# Ethernet.net
KiCad netlist of a schematic drawn in Altium Designer
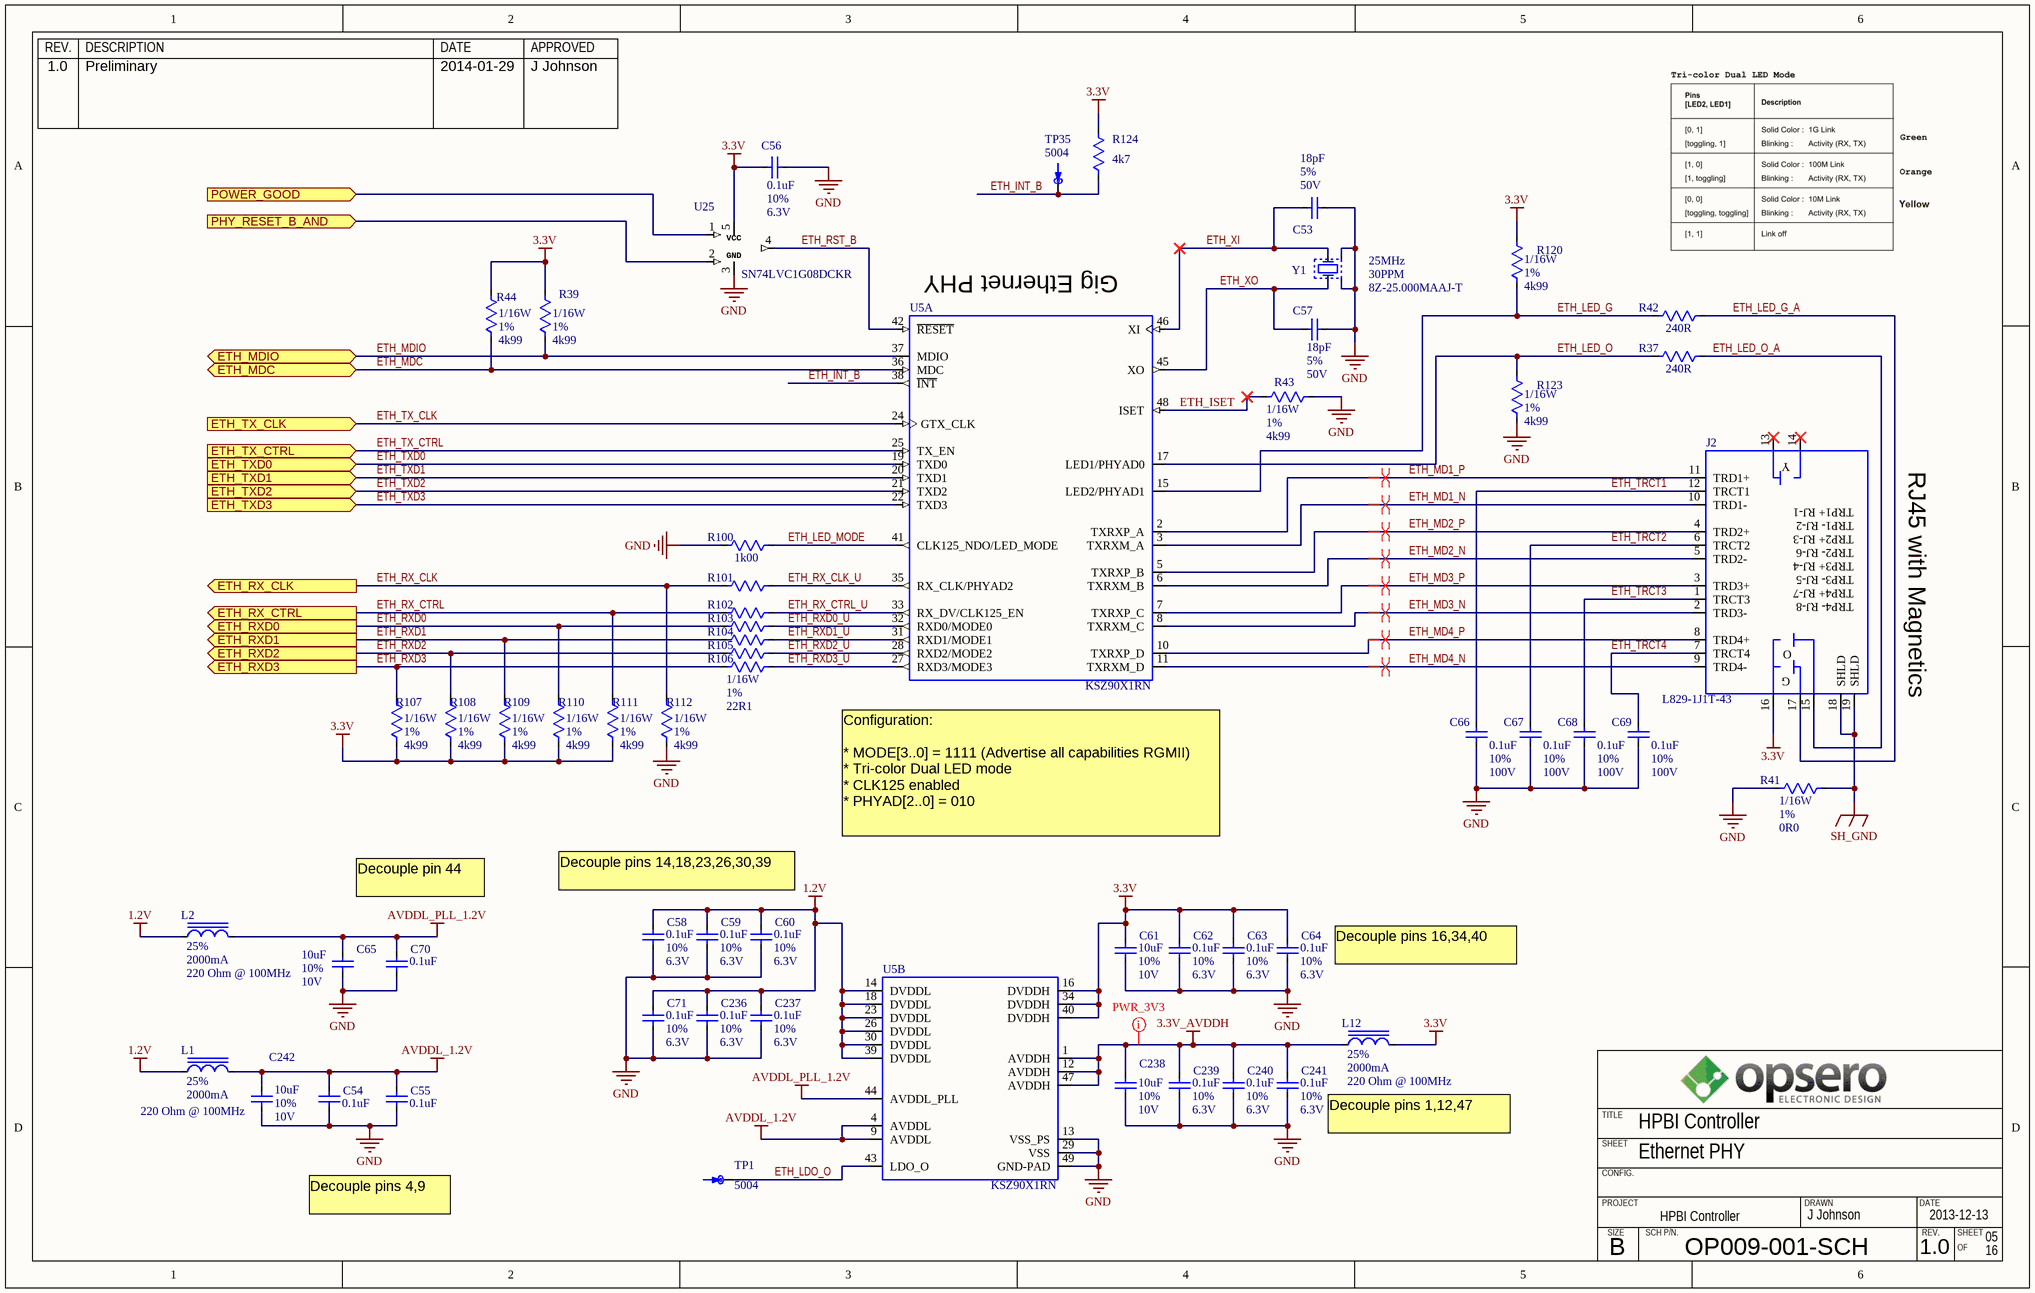
[diagram p0: Ethernet.SchDoc]

(export (version "E")
  (design (tool "Eeschema 10.0.6"))
  (components
    (comp (ref "C53")
      (value "18pF")
      (footprint "CAPC1005X33N")
      (description "Capacitor ceramic, C0G (NP0), 18pF, 50V, 5%, -55 to +125 C, EIA0402")
      (fields
        (field (name "TOLERANCE") "5%")
        (field (name "VOLTAGE") "50V")
        (field (name "Comment") "CAPACITOR_NP_TYPE1")
      )
      (libsource (lib "parts") (part "CAPACITOR_NP_TYPE1"))
    )
    (comp (ref "C54")
      (value "0.1uF")
      (footprint "CAPC0603X33N")
      (description "Capacitor ceramic, X5R, 0.1uF, 6.3V, 10%, -55 to +125 C, EIA0201")
      (fields (field (name "TOLERANCE") "10%") (field (name "VOLTAGE") "6.3V"))
      (libsource (lib "parts") (part "CAPACITOR_NP_TYPE1"))
    )
    (comp (ref "C55")
      (value "0.1uF")
      (footprint "CAPC0603X33N")
      (description "Capacitor ceramic, X5R, 0.1uF, 6.3V, 10%, -55 to +125 C, EIA0201")
      (fields (field (name "TOLERANCE") "10%") (field (name "VOLTAGE") "6.3V"))
      (libsource (lib "parts") (part "CAPACITOR_NP_TYPE1"))
    )
    (comp (ref "C56")
      (value "0.1uF")
      (footprint "CAPC0603X33N")
      (description "Capacitor ceramic, X5R, 0.1uF, 6.3V, 10%, -55 to +125 C, EIA0201")
      (fields
        (field (name "TOLERANCE") "10%")
        (field (name "VOLTAGE") "6.3V")
        (field (name "Comment") "CAPACITOR_NP_TYPE1")
      )
      (libsource (lib "parts") (part "CAPACITOR_NP_TYPE1"))
    )
    (comp (ref "C57")
      (value "18pF")
      (footprint "CAPC1005X33N")
      (description "Capacitor ceramic, C0G (NP0), 18pF, 50V, 5%, -55 to +125 C, EIA0402")
      (fields
        (field (name "TOLERANCE") "5%")
        (field (name "VOLTAGE") "50V")
        (field (name "Comment") "CAPACITOR_NP_TYPE1")
      )
      (libsource (lib "parts") (part "CAPACITOR_NP_TYPE1"))
    )
    (comp (ref "C58")
      (value "0.1uF")
      (footprint "CAPC0603X33N")
      (description "Capacitor ceramic, X5R, 0.1uF, 6.3V, 10%, -55 to +125 C, EIA0201")
      (fields
        (field (name "TOLERANCE") "10%")
        (field (name "VOLTAGE") "6.3V")
        (field (name "Comment") "CAPACITOR_NP_TYPE1")
      )
      (libsource (lib "parts") (part "CAPACITOR_NP_TYPE1"))
    )
    (comp (ref "C59")
      (value "0.1uF")
      (footprint "CAPC0603X33N")
      (description "Capacitor ceramic, X5R, 0.1uF, 6.3V, 10%, -55 to +125 C, EIA0201")
      (fields
        (field (name "TOLERANCE") "10%")
        (field (name "VOLTAGE") "6.3V")
        (field (name "Comment") "CAPACITOR_NP_TYPE1")
      )
      (libsource (lib "parts") (part "CAPACITOR_NP_TYPE1"))
    )
    (comp (ref "C60")
      (value "0.1uF")
      (footprint "CAPC0603X33N")
      (description "Capacitor ceramic, X5R, 0.1uF, 6.3V, 10%, -55 to +125 C, EIA0201")
      (fields
        (field (name "TOLERANCE") "10%")
        (field (name "VOLTAGE") "6.3V")
        (field (name "Comment") "CAPACITOR_NP_TYPE1")
      )
      (libsource (lib "parts") (part "CAPACITOR_NP_TYPE1"))
    )
    (comp (ref "C61")
      (value "10uF")
      (footprint "CAPC1608X38N")
      (description "Capacitor ceramic, X5R, 10uF, 10V, 10%, -55 to +85 C, EIA0603")
      (fields
        (field (name "TOLERANCE") "10%")
        (field (name "VOLTAGE") "10V")
        (field (name "Comment") "CAPACITOR_NP_TYPE1")
      )
      (libsource (lib "parts") (part "CAPACITOR_NP_TYPE1"))
    )
    (comp (ref "C62")
      (value "0.1uF")
      (footprint "CAPC0603X33N")
      (description "Capacitor ceramic, X5R, 0.1uF, 6.3V, 10%, -55 to +125 C, EIA0201")
      (fields
        (field (name "TOLERANCE") "10%")
        (field (name "VOLTAGE") "6.3V")
        (field (name "Comment") "CAPACITOR_NP_TYPE1")
      )
      (libsource (lib "parts") (part "CAPACITOR_NP_TYPE1"))
    )
    (comp (ref "C63")
      (value "0.1uF")
      (footprint "CAPC0603X33N")
      (description "Capacitor ceramic, X5R, 0.1uF, 6.3V, 10%, -55 to +125 C, EIA0201")
      (fields
        (field (name "TOLERANCE") "10%")
        (field (name "VOLTAGE") "6.3V")
        (field (name "Comment") "CAPACITOR_NP_TYPE1")
      )
      (libsource (lib "parts") (part "CAPACITOR_NP_TYPE1"))
    )
    (comp (ref "C64")
      (value "0.1uF")
      (footprint "CAPC0603X33N")
      (description "Capacitor ceramic, X5R, 0.1uF, 6.3V, 10%, -55 to +125 C, EIA0201")
      (fields
        (field (name "TOLERANCE") "10%")
        (field (name "VOLTAGE") "6.3V")
        (field (name "Comment") "CAPACITOR_NP_TYPE1")
      )
      (libsource (lib "parts") (part "CAPACITOR_NP_TYPE1"))
    )
    (comp (ref "C65")
      (value "10uF")
      (footprint "CAPC1608X38N")
      (description "Capacitor ceramic, X5R, 10uF, 10V, 10%, -55 to +85 C, EIA0603")
      (fields
        (field (name "TOLERANCE") "10%")
        (field (name "VOLTAGE") "10V")
        (field (name "Comment") "CAPACITOR_NP_TYPE1")
      )
      (libsource (lib "parts") (part "CAPACITOR_NP_TYPE1"))
    )
    (comp (ref "C66")
      (value "0.1uF")
      (footprint "CAPC1608X38N")
      (description "Capacitor ceramic, X7R, 0.1uF, 100V, 10%, -55 to +125 C, EIA0603")
      (fields
        (field (name "TOLERANCE") "10%")
        (field (name "VOLTAGE") "100V")
        (field (name "Comment") "CAPACITOR_NP_TYPE1")
      )
      (libsource (lib "parts") (part "CAPACITOR_NP_TYPE1"))
    )
    (comp (ref "C67")
      (value "0.1uF")
      (footprint "CAPC1608X38N")
      (description "Capacitor ceramic, X7R, 0.1uF, 100V, 10%, -55 to +125 C, EIA0603")
      (fields
        (field (name "TOLERANCE") "10%")
        (field (name "VOLTAGE") "100V")
        (field (name "Comment") "CAPACITOR_NP_TYPE1")
      )
      (libsource (lib "parts") (part "CAPACITOR_NP_TYPE1"))
    )
    (comp (ref "C68")
      (value "0.1uF")
      (footprint "CAPC1608X38N")
      (description "Capacitor ceramic, X7R, 0.1uF, 100V, 10%, -55 to +125 C, EIA0603")
      (fields
        (field (name "TOLERANCE") "10%")
        (field (name "VOLTAGE") "100V")
        (field (name "Comment") "CAPACITOR_NP_TYPE1")
      )
      (libsource (lib "parts") (part "CAPACITOR_NP_TYPE1"))
    )
    (comp (ref "C69")
      (value "0.1uF")
      (footprint "CAPC1608X38N")
      (description "Capacitor ceramic, X7R, 0.1uF, 100V, 10%, -55 to +125 C, EIA0603")
      (fields
        (field (name "TOLERANCE") "10%")
        (field (name "VOLTAGE") "100V")
        (field (name "Comment") "CAPACITOR_NP_TYPE1")
      )
      (libsource (lib "parts") (part "CAPACITOR_NP_TYPE1"))
    )
    (comp (ref "C70")
      (value "0.1uF")
      (footprint "CAPC0603X33N")
      (description "Capacitor ceramic, X5R, 0.1uF, 6.3V, 10%, -55 to +125 C, EIA0201")
      (fields (field (name "TOLERANCE") "10%") (field (name "VOLTAGE") "6.3V"))
      (libsource (lib "parts") (part "CAPACITOR_NP_TYPE1"))
    )
    (comp (ref "C71")
      (value "0.1uF")
      (footprint "CAPC0603X33N")
      (description "Capacitor ceramic, X5R, 0.1uF, 6.3V, 10%, -55 to +125 C, EIA0201")
      (fields
        (field (name "TOLERANCE") "10%")
        (field (name "VOLTAGE") "6.3V")
        (field (name "Comment") "CAPACITOR_NP_TYPE1")
      )
      (libsource (lib "parts") (part "CAPACITOR_NP_TYPE1"))
    )
    (comp (ref "C236")
      (value "0.1uF")
      (footprint "CAPC0603X33N")
      (description "Capacitor ceramic, X5R, 0.1uF, 6.3V, 10%, -55 to +125 C, EIA0201")
      (fields
        (field (name "TOLERANCE") "10%")
        (field (name "VOLTAGE") "6.3V")
        (field (name "Comment") "CAPACITOR_NP_TYPE1")
      )
      (libsource (lib "parts") (part "CAPACITOR_NP_TYPE1"))
    )
    (comp (ref "C237")
      (value "0.1uF")
      (footprint "CAPC0603X33N")
      (description "Capacitor ceramic, X5R, 0.1uF, 6.3V, 10%, -55 to +125 C, EIA0201")
      (fields
        (field (name "TOLERANCE") "10%")
        (field (name "VOLTAGE") "6.3V")
        (field (name "Comment") "CAPACITOR_NP_TYPE1")
      )
      (libsource (lib "parts") (part "CAPACITOR_NP_TYPE1"))
    )
    (comp (ref "C238")
      (value "10uF")
      (footprint "CAPC1608X38N")
      (description "Capacitor ceramic, X5R, 10uF, 10V, 10%, -55 to +85 C, EIA0603")
      (fields
        (field (name "TOLERANCE") "10%")
        (field (name "VOLTAGE") "10V")
        (field (name "Comment") "CAPACITOR_NP_TYPE1")
      )
      (libsource (lib "parts") (part "CAPACITOR_NP_TYPE1"))
    )
    (comp (ref "C239")
      (value "0.1uF")
      (footprint "CAPC0603X33N")
      (description "Capacitor ceramic, X5R, 0.1uF, 6.3V, 10%, -55 to +125 C, EIA0201")
      (fields
        (field (name "TOLERANCE") "10%")
        (field (name "VOLTAGE") "6.3V")
        (field (name "Comment") "CAPACITOR_NP_TYPE1")
      )
      (libsource (lib "parts") (part "CAPACITOR_NP_TYPE1"))
    )
    (comp (ref "C240")
      (value "0.1uF")
      (footprint "CAPC0603X33N")
      (description "Capacitor ceramic, X5R, 0.1uF, 6.3V, 10%, -55 to +125 C, EIA0201")
      (fields
        (field (name "TOLERANCE") "10%")
        (field (name "VOLTAGE") "6.3V")
        (field (name "Comment") "CAPACITOR_NP_TYPE1")
      )
      (libsource (lib "parts") (part "CAPACITOR_NP_TYPE1"))
    )
    (comp (ref "C241")
      (value "0.1uF")
      (footprint "CAPC0603X33N")
      (description "Capacitor ceramic, X5R, 0.1uF, 6.3V, 10%, -55 to +125 C, EIA0201")
      (fields
        (field (name "TOLERANCE") "10%")
        (field (name "VOLTAGE") "6.3V")
        (field (name "Comment") "CAPACITOR_NP_TYPE1")
      )
      (libsource (lib "parts") (part "CAPACITOR_NP_TYPE1"))
    )
    (comp (ref "C242")
      (value "10uF")
      (footprint "CAPC1608X38N")
      (description "Capacitor ceramic, X5R, 10uF, 10V, 10%, -55 to +85 C, EIA0603")
      (fields
        (field (name "TOLERANCE") "10%")
        (field (name "VOLTAGE") "10V")
        (field (name "Comment") "CAPACITOR_NP_TYPE1")
      )
      (libsource (lib "parts") (part "CAPACITOR_NP_TYPE1"))
    )
    (comp (ref "J2")
      (value "L829-1J1T-43")
      (footprint "L829-1J1T-43")
      (description "Connector RJ45,10/100/1000, with Mag & 3 LED G/O/Y")
      (fields (field (name "POWER") "Pow") (field (name "VOLTAGE") "Vol"))
      (libsource (lib "parts") (part "CON_J_RJ45_MAG_TYPE_2"))
    )
    (comp (ref "L1")
      (value "220 Ohm @ 100MHz")
      (footprint "INDC2012X85N")
      (description "Ferrite chip, 220 Ohm @ 100MHz, 2000mA, 25%, -55 to +125 C, 0805")
      (fields
        (field (name "TOLERANCE") "25%")
        (field (name "CURRENT") "2000mA")
        (field (name "Comment") "INDUCTOR_CORE_TYPE1")
      )
      (libsource (lib "parts") (part "INDUCTOR_CORE_TYPE1"))
    )
    (comp (ref "L2")
      (value "220 Ohm @ 100MHz")
      (footprint "INDC2012X85N")
      (description "Ferrite chip, 220 Ohm @ 100MHz, 2000mA, 25%, -55 to +125 C, 0805")
      (fields
        (field (name "TOLERANCE") "25%")
        (field (name "CURRENT") "2000mA")
        (field (name "Comment") "INDUCTOR_CORE_TYPE1")
      )
      (libsource (lib "parts") (part "INDUCTOR_CORE_TYPE1"))
    )
    (comp (ref "L12")
      (value "220 Ohm @ 100MHz")
      (footprint "INDC2012X85N")
      (description "Ferrite chip, 220 Ohm @ 100MHz, 2000mA, 25%, -55 to +125 C, 0805")
      (fields
        (field (name "TOLERANCE") "25%")
        (field (name "CURRENT") "2000mA")
        (field (name "Comment") "INDUCTOR_CORE_TYPE1")
      )
      (libsource (lib "parts") (part "INDUCTOR_CORE_TYPE1"))
    )
    (comp (ref "R37")
      (value "240R")
      (footprint "RESC1005X33N")
      (description "Resistor, 240R, 1/16W, 1%, -50 to +155 C, EIA0402, EIA(M)1005")
      (fields (field (name "VOLTAGE") "50V") (field (name "POWER") "1/16W"))
      (libsource (lib "parts") (part "RESISTOR_TYPE1"))
    )
    (comp (ref "R39")
      (value "4k99")
      (footprint "RESC1005X33N")
      (description "Resistor, 4k99, 1/16W, 1%, -50 to +155 C, EIA0402, EIA(M)1005")
      (fields (field (name "VOLTAGE") "50V") (field (name "POWER") "1/16W") (field (name "TOLERANCE") "1%"))
      (libsource (lib "parts") (part "RESISTOR_TYPE1"))
    )
    (comp (ref "R41")
      (value "0R0")
      (footprint "RESC1005X33N")
      (description "Resistor, 0R0, 1/16W, 1%, -50 to +155 C, EIA0402, EIA(M)1005")
      (fields (field (name "VOLTAGE") "50V") (field (name "POWER") "1/16W") (field (name "TOLERANCE") "1%"))
      (libsource (lib "parts") (part "RESISTOR_TYPE1"))
    )
    (comp (ref "R42")
      (value "240R")
      (footprint "RESC1005X33N")
      (description "Resistor, 240R, 1/16W, 1%, -50 to +155 C, EIA0402, EIA(M)1005")
      (fields (field (name "VOLTAGE") "50V") (field (name "POWER") "1/16W"))
      (libsource (lib "parts") (part "RESISTOR_TYPE1"))
    )
    (comp (ref "R43")
      (value "4k99")
      (footprint "RESC1005X33N")
      (description "Resistor, 4k99, 1/16W, 1%, -50 to +155 C, EIA0402, EIA(M)1005")
      (fields (field (name "VOLTAGE") "50V") (field (name "POWER") "1/16W") (field (name "TOLERANCE") "1%"))
      (libsource (lib "parts") (part "RESISTOR_TYPE1"))
    )
    (comp (ref "R44")
      (value "4k99")
      (footprint "RESC1005X33N")
      (description "Resistor, 4k99, 1/16W, 1%, -50 to +155 C, EIA0402, EIA(M)1005")
      (fields (field (name "VOLTAGE") "50V") (field (name "POWER") "1/16W") (field (name "TOLERANCE") "1%"))
      (libsource (lib "parts") (part "RESISTOR_TYPE1"))
    )
    (comp (ref "R100")
      (value "1k00")
      (footprint "RESC1005X33N")
      (description "Resistor, 1k00, 1/16W, 1%, -55 to +155 C, EIA0402")
      (fields (field (name "VOLTAGE") "50V") (field (name "POWER") "1/16W"))
      (libsource (lib "parts") (part "RESISTOR_TYPE1"))
    )
    (comp (ref "R101")
      (value "*")
      (footprint "RESC1005X33N")
      (description "Resistor, 22R1, 1/16W, 1%, -55 to +155 C, EIA0402")
      (fields (field (name "VOLTAGE") "50V") (field (name "POWER") "1/16W"))
      (libsource (lib "parts") (part "RESISTOR_TYPE1"))
    )
    (comp (ref "R102")
      (value "*")
      (footprint "RESC1005X33N")
      (description "Resistor, 22R1, 1/16W, 1%, -55 to +155 C, EIA0402")
      (fields (field (name "VOLTAGE") "50V") (field (name "POWER") "1/16W"))
      (libsource (lib "parts") (part "RESISTOR_TYPE1"))
    )
    (comp (ref "R103")
      (value "*")
      (footprint "RESC1005X33N")
      (description "Resistor, 22R1, 1/16W, 1%, -55 to +155 C, EIA0402")
      (fields (field (name "VOLTAGE") "50V") (field (name "POWER") "1/16W"))
      (libsource (lib "parts") (part "RESISTOR_TYPE1"))
    )
    (comp (ref "R104")
      (value "*")
      (footprint "RESC1005X33N")
      (description "Resistor, 22R1, 1/16W, 1%, -55 to +155 C, EIA0402")
      (fields (field (name "VOLTAGE") "50V") (field (name "POWER") "1/16W"))
      (libsource (lib "parts") (part "RESISTOR_TYPE1"))
    )
    (comp (ref "R105")
      (value "*")
      (footprint "RESC1005X33N")
      (description "Resistor, 22R1, 1/16W, 1%, -55 to +155 C, EIA0402")
      (fields (field (name "VOLTAGE") "50V") (field (name "POWER") "1/16W"))
      (libsource (lib "parts") (part "RESISTOR_TYPE1"))
    )
    (comp (ref "R106")
      (value "22R1")
      (footprint "RESC1005X33N")
      (description "Resistor, 22R1, 1/16W, 1%, -55 to +155 C, EIA0402")
      (fields (field (name "VOLTAGE") "50V") (field (name "POWER") "1/16W") (field (name "TOLERANCE") "1%"))
      (libsource (lib "parts") (part "RESISTOR_TYPE1"))
    )
    (comp (ref "R107")
      (value "4k99")
      (footprint "RESC1005X33N")
      (description "Resistor, 4k99, 1/16W, 1%, -50 to +155 C, EIA0402, EIA(M)1005")
      (fields (field (name "VOLTAGE") "50V") (field (name "POWER") "1/16W") (field (name "TOLERANCE") "1%"))
      (libsource (lib "parts") (part "RESISTOR_TYPE1"))
    )
    (comp (ref "R108")
      (value "4k99")
      (footprint "RESC1005X33N")
      (description "Resistor, 4k99, 1/16W, 1%, -50 to +155 C, EIA0402, EIA(M)1005")
      (fields (field (name "VOLTAGE") "50V") (field (name "POWER") "1/16W") (field (name "TOLERANCE") "1%"))
      (libsource (lib "parts") (part "RESISTOR_TYPE1"))
    )
    (comp (ref "R109")
      (value "4k99")
      (footprint "RESC1005X33N")
      (description "Resistor, 4k99, 1/16W, 1%, -50 to +155 C, EIA0402, EIA(M)1005")
      (fields (field (name "VOLTAGE") "50V") (field (name "POWER") "1/16W") (field (name "TOLERANCE") "1%"))
      (libsource (lib "parts") (part "RESISTOR_TYPE1"))
    )
    (comp (ref "R110")
      (value "4k99")
      (footprint "RESC1005X33N")
      (description "Resistor, 4k99, 1/16W, 1%, -50 to +155 C, EIA0402, EIA(M)1005")
      (fields (field (name "VOLTAGE") "50V") (field (name "POWER") "1/16W") (field (name "TOLERANCE") "1%"))
      (libsource (lib "parts") (part "RESISTOR_TYPE1"))
    )
    (comp (ref "R111")
      (value "4k99")
      (footprint "RESC1005X33N")
      (description "Resistor, 4k99, 1/16W, 1%, -50 to +155 C, EIA0402, EIA(M)1005")
      (fields (field (name "VOLTAGE") "50V") (field (name "POWER") "1/16W") (field (name "TOLERANCE") "1%"))
      (libsource (lib "parts") (part "RESISTOR_TYPE1"))
    )
    (comp (ref "R112")
      (value "4k99")
      (footprint "RESC1005X33N")
      (description "Resistor, 4k99, 1/16W, 1%, -50 to +155 C, EIA0402, EIA(M)1005")
      (fields (field (name "VOLTAGE") "50V") (field (name "POWER") "1/16W") (field (name "TOLERANCE") "1%"))
      (libsource (lib "parts") (part "RESISTOR_TYPE1"))
    )
    (comp (ref "R120")
      (value "4k99")
      (footprint "RESC1005X33N")
      (description "Resistor, 4k99, 1/16W, 1%, -50 to +155 C, EIA0402, EIA(M)1005")
      (fields (field (name "VOLTAGE") "50V") (field (name "POWER") "1/16W") (field (name "TOLERANCE") "1%"))
      (libsource (lib "parts") (part "RESISTOR_TYPE1"))
    )
    (comp (ref "R123")
      (value "4k99")
      (footprint "RESC1005X33N")
      (description "Resistor, 4k99, 1/16W, 1%, -50 to +155 C, EIA0402, EIA(M)1005")
      (fields (field (name "VOLTAGE") "50V") (field (name "POWER") "1/16W") (field (name "TOLERANCE") "1%"))
      (libsource (lib "parts") (part "RESISTOR_TYPE1"))
    )
    (comp (ref "R124")
      (value "4k7")
      (footprint "RESC1005X33N")
      (description "Resistor, 4k7, 1/16W, 1%, -55 to +155 C, EIA0402")
      (fields (field (name "VOLTAGE") "50V") (field (name "POWER") "1/16W"))
      (libsource (lib "parts") (part "RESISTOR_TYPE1"))
    )
    (comp (ref "TP1")
      (value "5004")
      (footprint "KEY_5004")
      (description "Test point bead, yellow, Keystone Electronics, Thru-hole,")
      (fields (field (name "POWER") "Pow") (field (name "VOLTAGE") "Vol"))
      (libsource (lib "") (part "TEST_POINT_TYPE4_1"))
    )
    (comp (ref "TP35")
      (value "5004")
      (footprint "KEY_5004")
      (description "Test point bead, yellow, Keystone Electronics, Thru-hole,")
      (fields (field (name "POWER") "Pow") (field (name "VOLTAGE") "Vol"))
      (libsource (lib "parts") (part "TEST_POINT_TYPE4"))
    )
    (comp (ref "U5")
      (value "KSZ90X1RN")
      (footprint "QFN50P700X700X90-49N")
      (description "10/100/1000 ethernet PHY with RGMII, 3.3V,1.2V, 0, -40 to +85 C, 0, QFN48")
      (fields (field (name "POWER") "0") (field (name "VOLTAGE") "3.3V,1.2V"))
      (libsource (lib "parts") (part "KSZ90X1RN"))
    )
    (comp (ref "U25")
      (value "SN74LVC1G08DCKR")
      (footprint "SOT65P210X110-5N")
      (description "Single 2-input AND gate, 1.65V to 5.5V")
      (fields (field (name "POWER") "Pow") (field (name "VOLTAGE") "1.65V to 5.5V"))
      (libsource (lib "parts") (part "SN74LVC1G08"))
    )
    (comp (ref "Y1")
      (value "25MHz")
      (footprint "OSCSC185P200X250X55-4N")
      (description "Crystal, 25MHz, 30ppm, 100uW, -40 to +85 C, SMT")
      (fields
        (field (name "POWER") "100uW")
        (field (name "TOLERANCE") "30PPM")
        (field (name "MFG PART NUMBER 1") "8Z-25.000MAAJ-T")
      )
      (libsource (lib "parts") (part "XTAL_TYPE3"))
    )
  )
  (nets
    (net (code "1") (name "/ETH_INT_B") (class "Default")
      (node (ref "R124") (pin "2") (pinfunction "2_2") (pintype "passive"))
      (node (ref "TP35") (pin "1") (pinfunction "1_1") (pintype "passive"))
      (node (ref "U5") (pin "38") (pinfunction "~{INT}_38") (pintype "output"))
    )
    (net (code "2") (name "/ETH_ISET") (class "Default")
      (node (ref "R43") (pin "2") (pinfunction "2_2") (pintype "passive"))
      (node (ref "U5") (pin "48") (pinfunction "ISET_48") (pintype "input"))
    )
    (net (code "3") (name "/ETH_LDO_O") (class "Default")
      (node (ref "TP1") (pin "1") (pinfunction "1_1") (pintype "passive"))
      (node (ref "U5") (pin "43") (pinfunction "LDO_O_43") (pintype "power_in"))
    )
    (net (code "4") (name "/ETH_LED_G") (class "Default")
      (node (ref "R120") (pin "1") (pinfunction "1_1") (pintype "passive"))
      (node (ref "R42") (pin "1") (pinfunction "1_1") (pintype "passive"))
      (node (ref "U5") (pin "15") (pinfunction "LED2/PHYAD1_15") (pintype "bidirectional"))
    )
    (net (code "5") (name "/ETH_LED_G_A") (class "Default")
      (node (ref "J2") (pin "17") (pinfunction "K1_17") (pintype "passive"))
      (node (ref "R42") (pin "2") (pinfunction "2_2") (pintype "passive"))
    )
    (net (code "6") (name "/ETH_LED_MODE") (class "Default")
      (node (ref "R100") (pin "2") (pinfunction "2_2") (pintype "passive"))
      (node (ref "U5") (pin "41") (pinfunction "CLK125_NDO/LED_MODE_41") (pintype "output"))
    )
    (net (code "7") (name "/ETH_LED_O") (class "Default")
      (node (ref "R123") (pin "2") (pinfunction "2_2") (pintype "passive"))
      (node (ref "R37") (pin "1") (pinfunction "1_1") (pintype "passive"))
      (node (ref "U5") (pin "17") (pinfunction "LED1/PHYAD0_17") (pintype "bidirectional"))
    )
    (net (code "8") (name "/ETH_LED_O_A") (class "Default")
      (node (ref "J2") (pin "15") (pinfunction "18_15") (pintype "passive"))
      (node (ref "R37") (pin "2") (pinfunction "2_2") (pintype "passive"))
    )
    (net (code "9") (name "/ETH_MD1_N") (class "Default")
      (node (ref "J2") (pin "10") (pinfunction "TRD1-_10") (pintype "bidirectional"))
      (node (ref "U5") (pin "3") (pinfunction "TXRXM_A_3") (pintype "bidirectional"))
    )
    (net (code "10") (name "/ETH_MD1_P") (class "Default")
      (node (ref "J2") (pin "11") (pinfunction "TRD1+_11") (pintype "bidirectional"))
      (node (ref "U5") (pin "2") (pinfunction "TXRXP_A_2") (pintype "bidirectional"))
    )
    (net (code "11") (name "/ETH_MD2_N") (class "Default")
      (node (ref "J2") (pin "5") (pinfunction "TRD2-_5") (pintype "bidirectional"))
      (node (ref "U5") (pin "6") (pinfunction "TXRXM_B_6") (pintype "bidirectional"))
    )
    (net (code "12") (name "/ETH_MD2_P") (class "Default")
      (node (ref "J2") (pin "4") (pinfunction "TRD2+_4") (pintype "bidirectional"))
      (node (ref "U5") (pin "5") (pinfunction "TXRXP_B_5") (pintype "bidirectional"))
    )
    (net (code "13") (name "/ETH_MD3_N") (class "Default")
      (node (ref "J2") (pin "2") (pinfunction "TRD3-_2") (pintype "bidirectional"))
      (node (ref "U5") (pin "8") (pinfunction "TXRXM_C_8") (pintype "bidirectional"))
    )
    (net (code "14") (name "/ETH_MD3_P") (class "Default")
      (node (ref "J2") (pin "3") (pinfunction "TRD3+_3") (pintype "bidirectional"))
      (node (ref "U5") (pin "7") (pinfunction "TXRXP_C_7") (pintype "bidirectional"))
    )
    (net (code "15") (name "/ETH_MD4_N") (class "Default")
      (node (ref "J2") (pin "9") (pinfunction "TRD4-_9") (pintype "bidirectional"))
      (node (ref "U5") (pin "11") (pinfunction "TXRXM_D_11") (pintype "bidirectional"))
    )
    (net (code "16") (name "/ETH_MD4_P") (class "Default")
      (node (ref "J2") (pin "8") (pinfunction "TRD4+_8") (pintype "bidirectional"))
      (node (ref "U5") (pin "10") (pinfunction "TXRXP_D_10") (pintype "bidirectional"))
    )
    (net (code "17") (name "/ETH_MDC") (class "Default")
      (node (ref "R44") (pin "1") (pinfunction "1_1") (pintype "passive"))
      (node (ref "U5") (pin "36") (pinfunction "MDC_36") (pintype "input"))
    )
    (net (code "18") (name "/ETH_MDIO") (class "Default")
      (node (ref "R39") (pin "1") (pinfunction "1_1") (pintype "passive"))
      (node (ref "U5") (pin "37") (pinfunction "MDIO_37") (pintype "bidirectional"))
    )
    (net (code "19") (name "/ETH_RST_B") (class "Default")
      (node (ref "U25") (pin "4") (pinfunction "Y_4") (pintype "output"))
      (node (ref "U5") (pin "42") (pinfunction "~{RESET}_42") (pintype "input"))
    )
    (net (code "20") (name "/ETH_RXD0") (class "Default")
      (node (ref "R103") (pin "1") (pinfunction "1_1") (pintype "passive"))
      (node (ref "R110") (pin "2") (pinfunction "2_2") (pintype "passive"))
    )
    (net (code "21") (name "/ETH_RXD0_U") (class "Default")
      (node (ref "R103") (pin "2") (pinfunction "2_2") (pintype "passive"))
      (node (ref "U5") (pin "32") (pinfunction "RXD0/MODE0_32") (pintype "output"))
    )
    (net (code "22") (name "/ETH_RXD1") (class "Default")
      (node (ref "R104") (pin "1") (pinfunction "1_1") (pintype "passive"))
      (node (ref "R109") (pin "2") (pinfunction "2_2") (pintype "passive"))
    )
    (net (code "23") (name "/ETH_RXD1_U") (class "Default")
      (node (ref "R104") (pin "2") (pinfunction "2_2") (pintype "passive"))
      (node (ref "U5") (pin "31") (pinfunction "RXD1/MODE1_31") (pintype "output"))
    )
    (net (code "24") (name "/ETH_RXD2") (class "Default")
      (node (ref "R105") (pin "1") (pinfunction "1_1") (pintype "passive"))
      (node (ref "R108") (pin "2") (pinfunction "2_2") (pintype "passive"))
    )
    (net (code "25") (name "/ETH_RXD2_U") (class "Default")
      (node (ref "R105") (pin "2") (pinfunction "2_2") (pintype "passive"))
      (node (ref "U5") (pin "28") (pinfunction "RXD2/MODE2_28") (pintype "output"))
    )
    (net (code "26") (name "/ETH_RXD3") (class "Default")
      (node (ref "R106") (pin "1") (pinfunction "1_1") (pintype "passive"))
      (node (ref "R107") (pin "2") (pinfunction "2_2") (pintype "passive"))
    )
    (net (code "27") (name "/ETH_RXD3_U") (class "Default")
      (node (ref "R106") (pin "2") (pinfunction "2_2") (pintype "passive"))
      (node (ref "U5") (pin "27") (pinfunction "RXD3/MODE3_27") (pintype "output"))
    )
    (net (code "28") (name "/ETH_RX_CLK") (class "Default")
      (node (ref "R101") (pin "1") (pinfunction "1_1") (pintype "passive"))
      (node (ref "R112") (pin "2") (pinfunction "2_2") (pintype "passive"))
    )
    (net (code "29") (name "/ETH_RX_CLK_U") (class "Default")
      (node (ref "R101") (pin "2") (pinfunction "2_2") (pintype "passive"))
      (node (ref "U5") (pin "35") (pinfunction "RX_CLK/PHYAD2_35") (pintype "output"))
    )
    (net (code "30") (name "/ETH_RX_CTRL") (class "Default")
      (node (ref "R102") (pin "1") (pinfunction "1_1") (pintype "passive"))
      (node (ref "R111") (pin "2") (pinfunction "2_2") (pintype "passive"))
    )
    (net (code "31") (name "/ETH_RX_CTRL_U") (class "Default")
      (node (ref "R102") (pin "2") (pinfunction "2_2") (pintype "passive"))
      (node (ref "U5") (pin "33") (pinfunction "RX_DV/CLK125_EN_33") (pintype "output"))
    )
    (net (code "32") (name "/ETH_TRCT1") (class "Default")
      (node (ref "C66") (pin "1") (pinfunction "1_1") (pintype "passive"))
      (node (ref "J2") (pin "12") (pinfunction "TRCT1_12") (pintype "passive"))
    )
    (net (code "33") (name "/ETH_TRCT2") (class "Default")
      (node (ref "C67") (pin "1") (pinfunction "1_1") (pintype "passive"))
      (node (ref "J2") (pin "6") (pinfunction "TRCT2_6") (pintype "passive"))
    )
    (net (code "34") (name "/ETH_TRCT3") (class "Default")
      (node (ref "C68") (pin "1") (pinfunction "1_1") (pintype "passive"))
      (node (ref "J2") (pin "1") (pinfunction "TRCT3_1") (pintype "passive"))
    )
    (net (code "35") (name "/ETH_TRCT4") (class "Default")
      (node (ref "C69") (pin "1") (pinfunction "1_1") (pintype "passive"))
      (node (ref "J2") (pin "7") (pinfunction "TRCT4_7") (pintype "passive"))
    )
    (net (code "36") (name "/ETH_TXD0") (class "Default")
      (node (ref "U5") (pin "19") (pinfunction "TXD0_19") (pintype "input"))
    )
    (net (code "37") (name "/ETH_TXD1") (class "Default")
      (node (ref "U5") (pin "20") (pinfunction "TXD1_20") (pintype "input"))
    )
    (net (code "38") (name "/ETH_TXD2") (class "Default")
      (node (ref "U5") (pin "21") (pinfunction "TXD2_21") (pintype "input"))
    )
    (net (code "39") (name "/ETH_TXD3") (class "Default")
      (node (ref "U5") (pin "22") (pinfunction "TXD3_22") (pintype "input"))
    )
    (net (code "40") (name "/ETH_TX_CLK") (class "Default")
      (node (ref "U5") (pin "24") (pinfunction "GTX_CLK_24") (pintype "input"))
    )
    (net (code "41") (name "/ETH_TX_CTRL") (class "Default")
      (node (ref "U5") (pin "25") (pinfunction "TX_EN_25") (pintype "input"))
    )
    (net (code "42") (name "/ETH_XI") (class "Default")
      (node (ref "C53") (pin "1") (pinfunction "1_1") (pintype "passive"))
      (node (ref "U5") (pin "46") (pinfunction "XI_46") (pintype "input"))
      (node (ref "Y1") (pin "3") (pinfunction "3_3") (pintype "passive"))
    )
    (net (code "43") (name "/ETH_XO") (class "Default")
      (node (ref "C57") (pin "1") (pinfunction "1_1") (pintype "passive"))
      (node (ref "U5") (pin "45") (pinfunction "XO_45") (pintype "output"))
      (node (ref "Y1") (pin "1") (pinfunction "1_1") (pintype "passive"))
    )
    (net (code "44") (name "/PHY_RESET_B_AND") (class "Default")
      (node (ref "U25") (pin "2") (pinfunction "B_2") (pintype "input"))
    )
    (net (code "45") (name "/POWER_GOOD") (class "Default")
      (node (ref "U25") (pin "1") (pinfunction "A_1") (pintype "input"))
    )
    (net (code "46") (name "1.2V") (class "Default")
      (node (ref "C236") (pin "1") (pinfunction "1_1") (pintype "passive"))
      (node (ref "C237") (pin "1") (pinfunction "1_1") (pintype "passive"))
      (node (ref "C58") (pin "1") (pinfunction "1_1") (pintype "passive"))
      (node (ref "C59") (pin "1") (pinfunction "1_1") (pintype "passive"))
      (node (ref "C60") (pin "1") (pinfunction "1_1") (pintype "passive"))
      (node (ref "C71") (pin "1") (pinfunction "1_1") (pintype "passive"))
      (node (ref "L1") (pin "1") (pinfunction "1_1") (pintype "passive"))
      (node (ref "L2") (pin "1") (pinfunction "1_1") (pintype "passive"))
      (node (ref "U5") (pin "14") (pinfunction "DVDDL_14") (pintype "power_in"))
      (node (ref "U5") (pin "18") (pinfunction "DVDDL_18") (pintype "power_in"))
      (node (ref "U5") (pin "23") (pinfunction "DVDDL_23") (pintype "power_in"))
      (node (ref "U5") (pin "26") (pinfunction "DVDDL_26") (pintype "power_in"))
      (node (ref "U5") (pin "30") (pinfunction "DVDDL_30") (pintype "power_in"))
      (node (ref "U5") (pin "39") (pinfunction "DVDDL_39") (pintype "power_in"))
    )
    (net (code "47") (name "3.3V") (class "Default")
      (node (ref "C56") (pin "1") (pinfunction "1_1") (pintype "passive"))
      (node (ref "C61") (pin "1") (pinfunction "1_1") (pintype "passive"))
      (node (ref "C62") (pin "1") (pinfunction "1_1") (pintype "passive"))
      (node (ref "C63") (pin "1") (pinfunction "1_1") (pintype "passive"))
      (node (ref "C64") (pin "1") (pinfunction "1_1") (pintype "passive"))
      (node (ref "J2") (pin "16") (pinfunction "A1_16") (pintype "passive"))
      (node (ref "L12") (pin "2") (pinfunction "2_2") (pintype "passive"))
      (node (ref "R107") (pin "1") (pinfunction "1_1") (pintype "passive"))
      (node (ref "R108") (pin "1") (pinfunction "1_1") (pintype "passive"))
      (node (ref "R109") (pin "1") (pinfunction "1_1") (pintype "passive"))
      (node (ref "R110") (pin "1") (pinfunction "1_1") (pintype "passive"))
      (node (ref "R111") (pin "1") (pinfunction "1_1") (pintype "passive"))
      (node (ref "R120") (pin "2") (pinfunction "2_2") (pintype "passive"))
      (node (ref "R124") (pin "1") (pinfunction "1_1") (pintype "passive"))
      (node (ref "R39") (pin "2") (pinfunction "2_2") (pintype "passive"))
      (node (ref "R44") (pin "2") (pinfunction "2_2") (pintype "passive"))
      (node (ref "U25") (pin "5") (pinfunction "VCC_5") (pintype "power_in"))
      (node (ref "U5") (pin "16") (pinfunction "DVDDH_16") (pintype "power_in"))
      (node (ref "U5") (pin "34") (pinfunction "DVDDH_34") (pintype "power_in"))
      (node (ref "U5") (pin "40") (pinfunction "DVDDH_40") (pintype "power_in"))
    )
    (net (code "48") (name "3.3V_AVDDH") (class "Default")
      (node (ref "C238") (pin "1") (pinfunction "1_1") (pintype "passive"))
      (node (ref "C239") (pin "1") (pinfunction "1_1") (pintype "passive"))
      (node (ref "C240") (pin "1") (pinfunction "1_1") (pintype "passive"))
      (node (ref "C241") (pin "1") (pinfunction "1_1") (pintype "passive"))
      (node (ref "L12") (pin "1") (pinfunction "1_1") (pintype "passive"))
      (node (ref "U5") (pin "1") (pinfunction "AVDDH_1") (pintype "power_in"))
      (node (ref "U5") (pin "12") (pinfunction "AVDDH_12") (pintype "power_in"))
      (node (ref "U5") (pin "47") (pinfunction "AVDDH_47") (pintype "power_in"))
    )
    (net (code "49") (name "AVDDL_1.2V") (class "Default")
      (node (ref "C242") (pin "1") (pinfunction "1_1") (pintype "passive"))
      (node (ref "C54") (pin "1") (pinfunction "1_1") (pintype "passive"))
      (node (ref "C55") (pin "1") (pinfunction "1_1") (pintype "passive"))
      (node (ref "L1") (pin "2") (pinfunction "2_2") (pintype "passive"))
      (node (ref "U5") (pin "4") (pinfunction "AVDDL_4") (pintype "power_in"))
      (node (ref "U5") (pin "9") (pinfunction "AVDDL_9") (pintype "power_in"))
    )
    (net (code "50") (name "AVDDL_PLL_1.2V") (class "Default")
      (node (ref "C65") (pin "1") (pinfunction "1_1") (pintype "passive"))
      (node (ref "C70") (pin "1") (pinfunction "1_1") (pintype "passive"))
      (node (ref "L2") (pin "2") (pinfunction "2_2") (pintype "passive"))
      (node (ref "U5") (pin "44") (pinfunction "AVDDL_PLL_44") (pintype "power_in"))
    )
    (net (code "51") (name "GND") (class "Default")
      (node (ref "C236") (pin "2") (pinfunction "2_2") (pintype "passive"))
      (node (ref "C237") (pin "2") (pinfunction "2_2") (pintype "passive"))
      (node (ref "C238") (pin "2") (pinfunction "2_2") (pintype "passive"))
      (node (ref "C239") (pin "2") (pinfunction "2_2") (pintype "passive"))
      (node (ref "C240") (pin "2") (pinfunction "2_2") (pintype "passive"))
      (node (ref "C241") (pin "2") (pinfunction "2_2") (pintype "passive"))
      (node (ref "C242") (pin "2") (pinfunction "2_2") (pintype "passive"))
      (node (ref "C53") (pin "2") (pinfunction "2_2") (pintype "passive"))
      (node (ref "C54") (pin "2") (pinfunction "2_2") (pintype "passive"))
      (node (ref "C55") (pin "2") (pinfunction "2_2") (pintype "passive"))
      (node (ref "C56") (pin "2") (pinfunction "2_2") (pintype "passive"))
      (node (ref "C57") (pin "2") (pinfunction "2_2") (pintype "passive"))
      (node (ref "C58") (pin "2") (pinfunction "2_2") (pintype "passive"))
      (node (ref "C59") (pin "2") (pinfunction "2_2") (pintype "passive"))
      (node (ref "C60") (pin "2") (pinfunction "2_2") (pintype "passive"))
      (node (ref "C61") (pin "2") (pinfunction "2_2") (pintype "passive"))
      (node (ref "C62") (pin "2") (pinfunction "2_2") (pintype "passive"))
      (node (ref "C63") (pin "2") (pinfunction "2_2") (pintype "passive"))
      (node (ref "C64") (pin "2") (pinfunction "2_2") (pintype "passive"))
      (node (ref "C65") (pin "2") (pinfunction "2_2") (pintype "passive"))
      (node (ref "C66") (pin "2") (pinfunction "2_2") (pintype "passive"))
      (node (ref "C67") (pin "2") (pinfunction "2_2") (pintype "passive"))
      (node (ref "C68") (pin "2") (pinfunction "2_2") (pintype "passive"))
      (node (ref "C69") (pin "2") (pinfunction "2_2") (pintype "passive"))
      (node (ref "C70") (pin "2") (pinfunction "2_2") (pintype "passive"))
      (node (ref "C71") (pin "2") (pinfunction "2_2") (pintype "passive"))
      (node (ref "R100") (pin "1") (pinfunction "1_1") (pintype "passive"))
      (node (ref "R112") (pin "1") (pinfunction "1_1") (pintype "passive"))
      (node (ref "R123") (pin "1") (pinfunction "1_1") (pintype "passive"))
      (node (ref "R41") (pin "1") (pinfunction "1_1") (pintype "passive"))
      (node (ref "R43") (pin "1") (pinfunction "1_1") (pintype "passive"))
      (node (ref "U25") (pin "3") (pinfunction "GND_3") (pintype "power_in"))
      (node (ref "U5") (pin "13") (pinfunction "VSS_PS_13") (pintype "power_in"))
      (node (ref "U5") (pin "29") (pinfunction "VSS_29") (pintype "power_in"))
      (node (ref "U5") (pin "49") (pinfunction "GND-PAD_49") (pintype "power_in"))
      (node (ref "Y1") (pin "2") (pinfunction "2_2") (pintype "passive"))
      (node (ref "Y1") (pin "4") (pinfunction "4_4") (pintype "passive"))
    )
    (net (code "52") (name "SH_GND") (class "Default")
      (node (ref "J2") (pin "18") (pinfunction "SHLD_18") (pintype "passive"))
      (node (ref "J2") (pin "19") (pinfunction "SHLD_19") (pintype "passive"))
      (node (ref "R41") (pin "2") (pinfunction "2_2") (pintype "passive"))
    )
    (net (code "53") (name "unconnected-(J2-A2-Pad14)") (class "Default")
      (node (ref "J2") (pin "14") (pinfunction "A2_14") (pintype "passive+no_connect"))
    )
    (net (code "54") (name "unconnected-(J2-K2-Pad13)") (class "Default")
      (node (ref "J2") (pin "13") (pinfunction "K2_13") (pintype "passive+no_connect"))
    )
  )
)
